# picopew.net
KiCad netlist of a schematic drawn in EAGLE
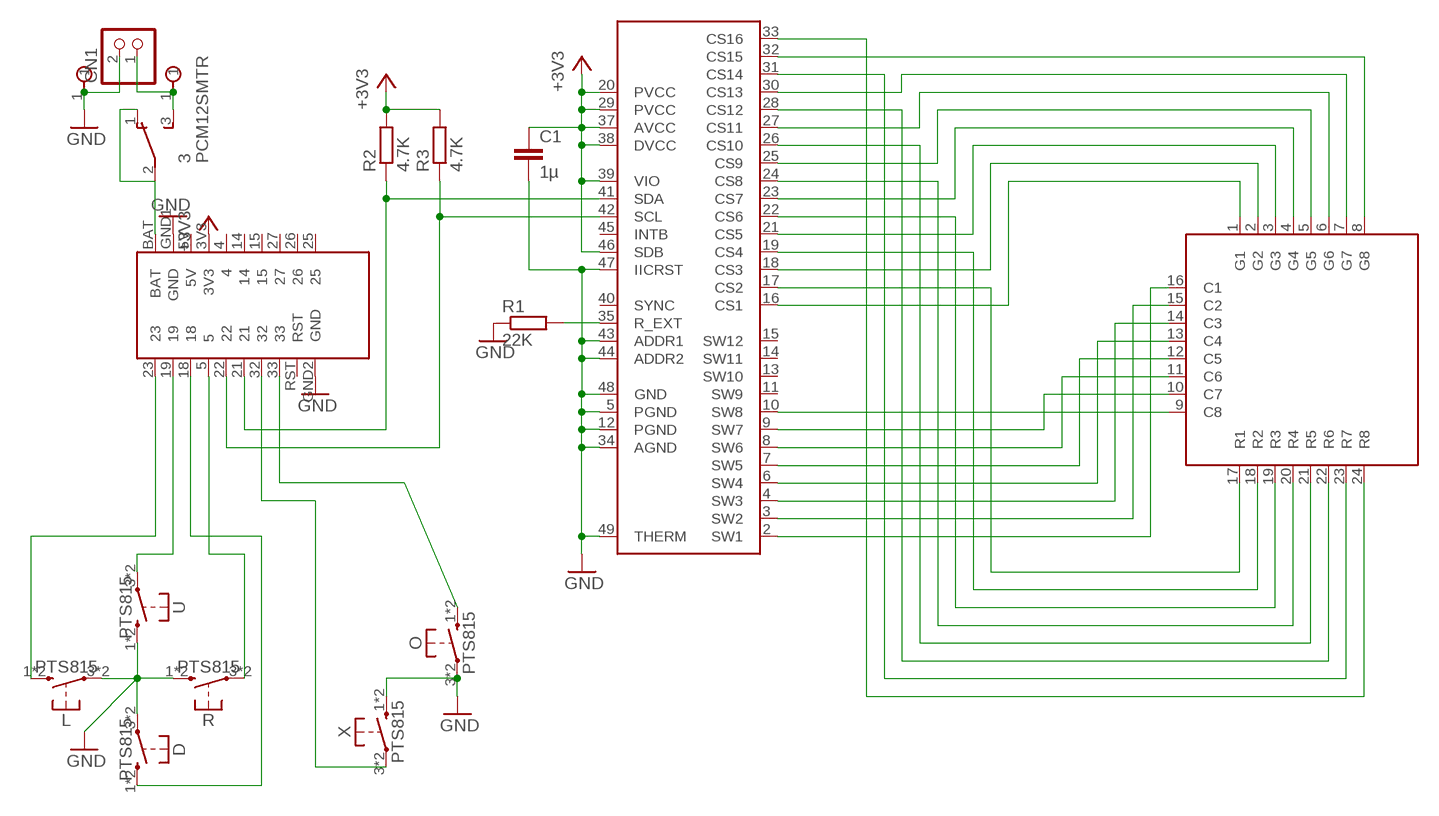
[diagram p0: schematic, sheet 1]

(export (version "E")
  (design (tool "Eeschema 10.0.6"))
  (components
    (comp (ref "1")
      (value "KYX-788AHG")
      (footprint "eagle-import:KYX-788AHG")
      (libsource (lib "eagle-import") (part "KYX-788AHG"))
    )
    (comp (ref "2")
      (value "TINYPICO")
      (footprint "eagle-import:TINYPICO")
      (libsource (lib "eagle-import") (part "TINYPICO"))
    )
    (comp (ref "3")
      (value "PCM12SMTR")
      (footprint "eagle-import:MICROSLIDESWITCH")
      (libsource (lib "eagle-import") (part "PCM12SMTR"))
    )
    (comp (ref "4")
      (value "SINGLEPAD")
      (footprint "eagle-import:SINGLEPAD")
      (libsource (lib "eagle-import") (part "SINGLEPAD"))
    )
    (comp (ref "5")
      (value "SINGLEPAD")
      (footprint "eagle-import:SINGLEPAD")
      (libsource (lib "eagle-import") (part "SINGLEPAD"))
    )
    (comp (ref "C1")
      (value "1µ")
      (footprint "eagle-import:C0805")
      (libsource (lib "eagle-import") (part "C-EUC0805"))
    )
    (comp (ref "CN1")
      (value "JST_2PIN-SMT-RA")
      (footprint "eagle-import:JST-PH-2-SMT-RA")
      (libsource (lib "eagle-import") (part "JST_2PIN-SMT-RA"))
    )
    (comp (ref "D")
      (value "PTS815")
      (footprint "eagle-import:MICROPUSHBUTTON")
      (libsource (lib "eagle-import") (part "PTS815"))
    )
    (comp (ref "L")
      (value "PTS815")
      (footprint "eagle-import:MICROPUSHBUTTON")
      (libsource (lib "eagle-import") (part "PTS815"))
    )
    (comp (ref "O")
      (value "PTS815")
      (footprint "eagle-import:MICROPUSHBUTTON")
      (libsource (lib "eagle-import") (part "PTS815"))
    )
    (comp (ref "R")
      (value "PTS815")
      (footprint "eagle-import:MICROPUSHBUTTON")
      (libsource (lib "eagle-import") (part "PTS815"))
    )
    (comp (ref "R1")
      (value "22K")
      (footprint "eagle-import:R0805")
      (libsource (lib "eagle-import") (part "R-EU_R0805"))
    )
    (comp (ref "R2")
      (value "4.7K")
      (footprint "eagle-import:R0805")
      (libsource (lib "eagle-import") (part "R-EU_R0805"))
    )
    (comp (ref "R3")
      (value "4.7K")
      (footprint "eagle-import:R0805")
      (libsource (lib "eagle-import") (part "R-EU_R0805"))
    )
    (comp (ref "U")
      (value "PTS815")
      (footprint "eagle-import:MICROPUSHBUTTON")
      (libsource (lib "eagle-import") (part "PTS815"))
    )
    (comp (ref "U1")
      (value "IS31FL3733-TQLS4")
      (footprint "eagle-import:TQFP48")
      (libsource (lib "eagle-import") (part "IS31FL3733-TQLS4"))
    )
    (comp (ref "X")
      (value "PTS815")
      (footprint "eagle-import:MICROPUSHBUTTON")
      (libsource (lib "eagle-import") (part "PTS815"))
    )
  )
  (nets
    (net (code "1") (name "+3V3") (class "Default")
      (node (ref "2") (pin "3V3") (pinfunction "3V3_3V3") (pintype "power_in"))
      (node (ref "C1") (pin "1") (pinfunction "1_1") (pintype "passive"))
      (node (ref "R2") (pin "2") (pinfunction "2_2") (pintype "passive"))
      (node (ref "R3") (pin "2") (pinfunction "2_2") (pintype "passive"))
      (node (ref "U1") (pin "20") (pinfunction "PVCC_20") (pintype "power_in"))
      (node (ref "U1") (pin "29") (pinfunction "PVCC_29") (pintype "power_in"))
      (node (ref "U1") (pin "37") (pinfunction "AVCC_37") (pintype "power_in"))
      (node (ref "U1") (pin "38") (pinfunction "DVCC_38") (pintype "power_in"))
      (node (ref "U1") (pin "39") (pinfunction "VIO_39") (pintype "power_in"))
      (node (ref "U1") (pin "46") (pinfunction "SDB_46") (pintype "input"))
    )
    (net (code "2") (name "/5V") (class "Default")
      (node (ref "2") (pin "5V") (pinfunction "5V_5V") (pintype "power_in"))
    )
    (net (code "3") (name "GND") (class "Default")
      (node (ref "2") (pin "GND1") (pinfunction "GND_GND1") (pintype "power_in"))
      (node (ref "2") (pin "GND2") (pinfunction "GND_GND2") (pintype "power_in"))
      (node (ref "5") (pin "1") (pinfunction "1_1") (pintype "passive"))
      (node (ref "C1") (pin "2") (pinfunction "2_2") (pintype "passive"))
      (node (ref "CN1") (pin "2") (pinfunction "1_2") (pintype "passive"))
      (node (ref "D") (pin "3") (pinfunction "P_3") (pintype "passive"))
      (node (ref "D") (pin "4") (pinfunction "P_4") (pintype "passive"))
      (node (ref "L") (pin "3") (pinfunction "P_3") (pintype "passive"))
      (node (ref "L") (pin "4") (pinfunction "P_4") (pintype "passive"))
      (node (ref "O") (pin "3") (pinfunction "P_3") (pintype "passive"))
      (node (ref "O") (pin "4") (pinfunction "P_4") (pintype "passive"))
      (node (ref "R") (pin "1") (pinfunction "S_1") (pintype "passive"))
      (node (ref "R") (pin "2") (pinfunction "S_2") (pintype "passive"))
      (node (ref "R1") (pin "1") (pinfunction "1_1") (pintype "passive"))
      (node (ref "U") (pin "1") (pinfunction "S_1") (pintype "passive"))
      (node (ref "U") (pin "2") (pinfunction "S_2") (pintype "passive"))
      (node (ref "U1") (pin "12") (pinfunction "PGND_12") (pintype "power_in"))
      (node (ref "U1") (pin "34") (pinfunction "AGND_34") (pintype "power_in"))
      (node (ref "U1") (pin "43") (pinfunction "ADDR1_43") (pintype "input"))
      (node (ref "U1") (pin "44") (pinfunction "ADDR2_44") (pintype "input"))
      (node (ref "U1") (pin "47") (pinfunction "IICRST_47") (pintype "input"))
      (node (ref "U1") (pin "48") (pinfunction "GND_48") (pintype "power_in"))
      (node (ref "U1") (pin "49") (pinfunction "THERM_49") (pintype "power_in"))
      (node (ref "U1") (pin "5") (pinfunction "PGND_5") (pintype "power_in"))
      (node (ref "X") (pin "1") (pinfunction "S_1") (pintype "passive"))
      (node (ref "X") (pin "2") (pinfunction "S_2") (pintype "passive"))
    )
    (net (code "4") (name "Net-(1-C1)") (class "Default")
      (node (ref "1") (pin "16") (pinfunction "C1_16") (pintype "passive"))
      (node (ref "U1") (pin "2") (pinfunction "SW1_2") (pintype "output"))
    )
    (net (code "5") (name "Net-(1-C2)") (class "Default")
      (node (ref "1") (pin "15") (pinfunction "C2_15") (pintype "passive"))
      (node (ref "U1") (pin "3") (pinfunction "SW2_3") (pintype "output"))
    )
    (net (code "6") (name "Net-(1-C3)") (class "Default")
      (node (ref "1") (pin "14") (pinfunction "C3_14") (pintype "passive"))
      (node (ref "U1") (pin "4") (pinfunction "SW3_4") (pintype "output"))
    )
    (net (code "7") (name "Net-(1-C4)") (class "Default")
      (node (ref "1") (pin "13") (pinfunction "C4_13") (pintype "passive"))
      (node (ref "U1") (pin "6") (pinfunction "SW4_6") (pintype "output"))
    )
    (net (code "8") (name "Net-(1-C5)") (class "Default")
      (node (ref "1") (pin "12") (pinfunction "C5_12") (pintype "passive"))
      (node (ref "U1") (pin "7") (pinfunction "SW5_7") (pintype "output"))
    )
    (net (code "9") (name "Net-(1-C6)") (class "Default")
      (node (ref "1") (pin "11") (pinfunction "C6_11") (pintype "passive"))
      (node (ref "U1") (pin "8") (pinfunction "SW6_8") (pintype "output"))
    )
    (net (code "10") (name "Net-(1-C7)") (class "Default")
      (node (ref "1") (pin "10") (pinfunction "C7_10") (pintype "passive"))
      (node (ref "U1") (pin "9") (pinfunction "SW7_9") (pintype "output"))
    )
    (net (code "11") (name "Net-(1-C8)") (class "Default")
      (node (ref "1") (pin "9") (pinfunction "C8_9") (pintype "passive"))
      (node (ref "U1") (pin "10") (pinfunction "SW8_10") (pintype "output"))
    )
    (net (code "12") (name "Net-(1-G1)") (class "Default")
      (node (ref "1") (pin "1") (pinfunction "G1_1") (pintype "passive"))
      (node (ref "U1") (pin "16") (pinfunction "CS1_16") (pintype "output"))
    )
    (net (code "13") (name "Net-(1-G2)") (class "Default")
      (node (ref "1") (pin "2") (pinfunction "G2_2") (pintype "passive"))
      (node (ref "U1") (pin "18") (pinfunction "CS3_18") (pintype "output"))
    )
    (net (code "14") (name "Net-(1-G3)") (class "Default")
      (node (ref "1") (pin "3") (pinfunction "G3_3") (pintype "passive"))
      (node (ref "U1") (pin "21") (pinfunction "CS5_21") (pintype "output"))
    )
    (net (code "15") (name "Net-(1-G4)") (class "Default")
      (node (ref "1") (pin "4") (pinfunction "G4_4") (pintype "passive"))
      (node (ref "U1") (pin "23") (pinfunction "CS7_23") (pintype "output"))
    )
    (net (code "16") (name "Net-(1-G5)") (class "Default")
      (node (ref "1") (pin "5") (pinfunction "G5_5") (pintype "passive"))
      (node (ref "U1") (pin "25") (pinfunction "CS9_25") (pintype "output"))
    )
    (net (code "17") (name "Net-(1-G6)") (class "Default")
      (node (ref "1") (pin "6") (pinfunction "G6_6") (pintype "passive"))
      (node (ref "U1") (pin "27") (pinfunction "CS11_27") (pintype "output"))
    )
    (net (code "18") (name "Net-(1-G7)") (class "Default")
      (node (ref "1") (pin "7") (pinfunction "G7_7") (pintype "passive"))
      (node (ref "U1") (pin "30") (pinfunction "CS13_30") (pintype "output"))
    )
    (net (code "19") (name "Net-(1-G8)") (class "Default")
      (node (ref "1") (pin "8") (pinfunction "G8_8") (pintype "passive"))
      (node (ref "U1") (pin "32") (pinfunction "CS15_32") (pintype "output"))
    )
    (net (code "20") (name "Net-(1-R1)") (class "Default")
      (node (ref "1") (pin "17") (pinfunction "R1_17") (pintype "passive"))
      (node (ref "U1") (pin "17") (pinfunction "CS2_17") (pintype "output"))
    )
    (net (code "21") (name "Net-(1-R2)") (class "Default")
      (node (ref "1") (pin "18") (pinfunction "R2_18") (pintype "passive"))
      (node (ref "U1") (pin "19") (pinfunction "CS4_19") (pintype "output"))
    )
    (net (code "22") (name "Net-(1-R3)") (class "Default")
      (node (ref "1") (pin "19") (pinfunction "R3_19") (pintype "passive"))
      (node (ref "U1") (pin "22") (pinfunction "CS6_22") (pintype "output"))
    )
    (net (code "23") (name "Net-(1-R4)") (class "Default")
      (node (ref "1") (pin "20") (pinfunction "R4_20") (pintype "passive"))
      (node (ref "U1") (pin "24") (pinfunction "CS8_24") (pintype "output"))
    )
    (net (code "24") (name "Net-(1-R5)") (class "Default")
      (node (ref "1") (pin "21") (pinfunction "R5_21") (pintype "passive"))
      (node (ref "U1") (pin "26") (pinfunction "CS10_26") (pintype "output"))
    )
    (net (code "25") (name "Net-(1-R6)") (class "Default")
      (node (ref "1") (pin "22") (pinfunction "R6_22") (pintype "passive"))
      (node (ref "U1") (pin "28") (pinfunction "CS12_28") (pintype "output"))
    )
    (net (code "26") (name "Net-(1-R7)") (class "Default")
      (node (ref "1") (pin "23") (pinfunction "R7_23") (pintype "passive"))
      (node (ref "U1") (pin "31") (pinfunction "CS14_31") (pintype "output"))
    )
    (net (code "27") (name "Net-(1-R8)") (class "Default")
      (node (ref "1") (pin "24") (pinfunction "R8_24") (pintype "passive"))
      (node (ref "U1") (pin "33") (pinfunction "CS16_33") (pintype "output"))
    )
    (net (code "28") (name "Net-(2-Pad5)") (class "Default")
      (node (ref "2") (pin "5") (pinfunction "5_5") (pintype "bidirectional"))
      (node (ref "R") (pin "3") (pinfunction "P_3") (pintype "passive"))
      (node (ref "R") (pin "4") (pinfunction "P_4") (pintype "passive"))
    )
    (net (code "29") (name "Net-(2-Pad18)") (class "Default")
      (node (ref "2") (pin "18") (pinfunction "18_18") (pintype "bidirectional"))
      (node (ref "D") (pin "1") (pinfunction "S_1") (pintype "passive"))
      (node (ref "D") (pin "2") (pinfunction "S_2") (pintype "passive"))
    )
    (net (code "30") (name "Net-(2-Pad19)") (class "Default")
      (node (ref "2") (pin "19") (pinfunction "19_19") (pintype "bidirectional"))
      (node (ref "U") (pin "3") (pinfunction "P_3") (pintype "passive"))
      (node (ref "U") (pin "4") (pinfunction "P_4") (pintype "passive"))
    )
    (net (code "31") (name "Net-(2-Pad23)") (class "Default")
      (node (ref "2") (pin "23") (pinfunction "23_23") (pintype "bidirectional"))
      (node (ref "L") (pin "1") (pinfunction "S_1") (pintype "passive"))
      (node (ref "L") (pin "2") (pinfunction "S_2") (pintype "passive"))
    )
    (net (code "32") (name "Net-(2-Pad32)") (class "Default")
      (node (ref "2") (pin "32") (pinfunction "32_32") (pintype "bidirectional"))
      (node (ref "X") (pin "3") (pinfunction "P_3") (pintype "passive"))
      (node (ref "X") (pin "4") (pinfunction "P_4") (pintype "passive"))
    )
    (net (code "33") (name "Net-(2-Pad33)") (class "Default")
      (node (ref "2") (pin "33") (pinfunction "33_33") (pintype "bidirectional"))
      (node (ref "O") (pin "1") (pinfunction "S_1") (pintype "passive"))
      (node (ref "O") (pin "2") (pinfunction "S_2") (pintype "passive"))
    )
    (net (code "34") (name "Net-(3-O)") (class "Default")
      (node (ref "2") (pin "BAT") (pinfunction "BAT_BAT") (pintype "power_in"))
      (node (ref "3") (pin "1") (pinfunction "O_1") (pintype "passive"))
      (node (ref "3") (pin "2") (pinfunction "P_2") (pintype "passive"))
    )
    (net (code "35") (name "Net-(3-S)") (class "Default")
      (node (ref "3") (pin "3") (pinfunction "S_3") (pintype "passive"))
      (node (ref "4") (pin "1") (pinfunction "1_1") (pintype "passive"))
      (node (ref "CN1") (pin "1") (pinfunction "2_1") (pintype "passive"))
    )
    (net (code "36") (name "Net-(U1-R_EXT)") (class "Default")
      (node (ref "R1") (pin "2") (pinfunction "2_2") (pintype "passive"))
      (node (ref "U1") (pin "35") (pinfunction "R_EXT_35") (pintype "bidirectional"))
    )
    (net (code "37") (name "Net-(U1-SCL)") (class "Default")
      (node (ref "2") (pin "22") (pinfunction "22_22") (pintype "bidirectional"))
      (node (ref "R3") (pin "1") (pinfunction "1_1") (pintype "passive"))
      (node (ref "U1") (pin "42") (pinfunction "SCL_42") (pintype "input"))
    )
    (net (code "38") (name "Net-(U1-SDA)") (class "Default")
      (node (ref "2") (pin "21") (pinfunction "21_21") (pintype "bidirectional"))
      (node (ref "R2") (pin "1") (pinfunction "1_1") (pintype "passive"))
      (node (ref "U1") (pin "41") (pinfunction "SDA_41") (pintype "bidirectional"))
    )
    (net (code "39") (name "unconnected-(2-Pad4)") (class "Default")
      (node (ref "2") (pin "4") (pinfunction "4_4") (pintype "bidirectional"))
    )
    (net (code "40") (name "unconnected-(2-Pad14)") (class "Default")
      (node (ref "2") (pin "14") (pinfunction "14_14") (pintype "bidirectional"))
    )
    (net (code "41") (name "unconnected-(2-Pad15)") (class "Default")
      (node (ref "2") (pin "15") (pinfunction "15_15") (pintype "bidirectional"))
    )
    (net (code "42") (name "unconnected-(2-Pad25)") (class "Default")
      (node (ref "2") (pin "25") (pinfunction "25_25") (pintype "bidirectional"))
    )
    (net (code "43") (name "unconnected-(2-Pad26)") (class "Default")
      (node (ref "2") (pin "26") (pinfunction "26_26") (pintype "bidirectional"))
    )
    (net (code "44") (name "unconnected-(2-Pad27)") (class "Default")
      (node (ref "2") (pin "27") (pinfunction "27_27") (pintype "bidirectional"))
    )
    (net (code "45") (name "unconnected-(2-PadRST)") (class "Default")
      (node (ref "2") (pin "RST") (pinfunction "RST_RST") (pintype "input"))
    )
    (net (code "46") (name "unconnected-(U1-INTB-Pad45)") (class "Default")
      (node (ref "U1") (pin "45") (pinfunction "INTB_45") (pintype "output"))
    )
    (net (code "47") (name "unconnected-(U1-SW9-Pad11)") (class "Default")
      (node (ref "U1") (pin "11") (pinfunction "SW9_11") (pintype "output"))
    )
    (net (code "48") (name "unconnected-(U1-SW10-Pad13)") (class "Default")
      (node (ref "U1") (pin "13") (pinfunction "SW10_13") (pintype "output"))
    )
    (net (code "49") (name "unconnected-(U1-SW11-Pad14)") (class "Default")
      (node (ref "U1") (pin "14") (pinfunction "SW11_14") (pintype "output"))
    )
    (net (code "50") (name "unconnected-(U1-SW12-Pad15)") (class "Default")
      (node (ref "U1") (pin "15") (pinfunction "SW12_15") (pintype "output"))
    )
    (net (code "51") (name "unconnected-(U1-SYNC-Pad40)") (class "Default")
      (node (ref "U1") (pin "40") (pinfunction "SYNC_40") (pintype "bidirectional"))
    )
  )
)
